# computeModuleDaughterV2.net
KiCad netlist of a schematic drawn in EAGLE
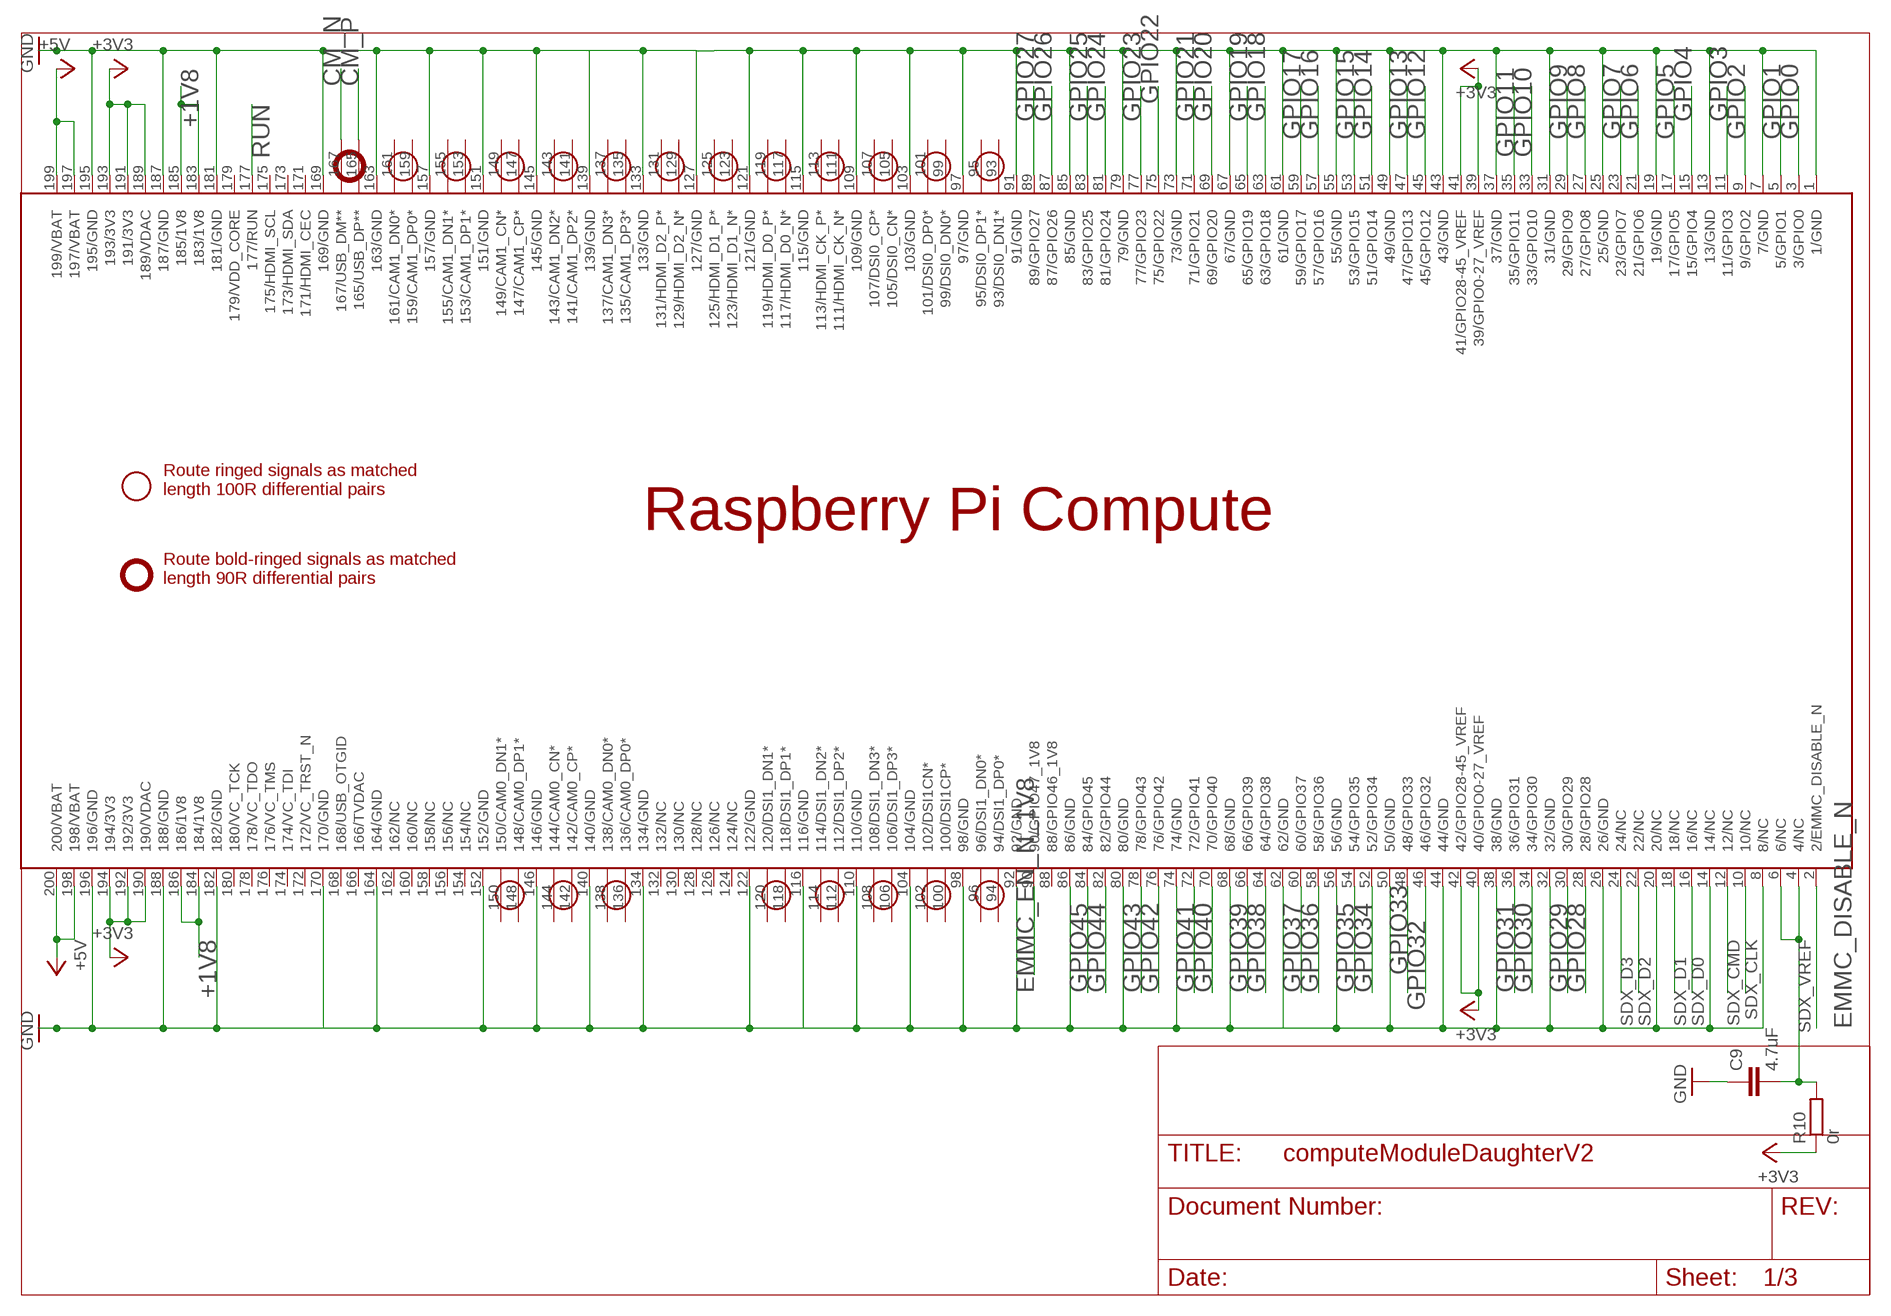
[diagram p0: schematic, sheet 1]
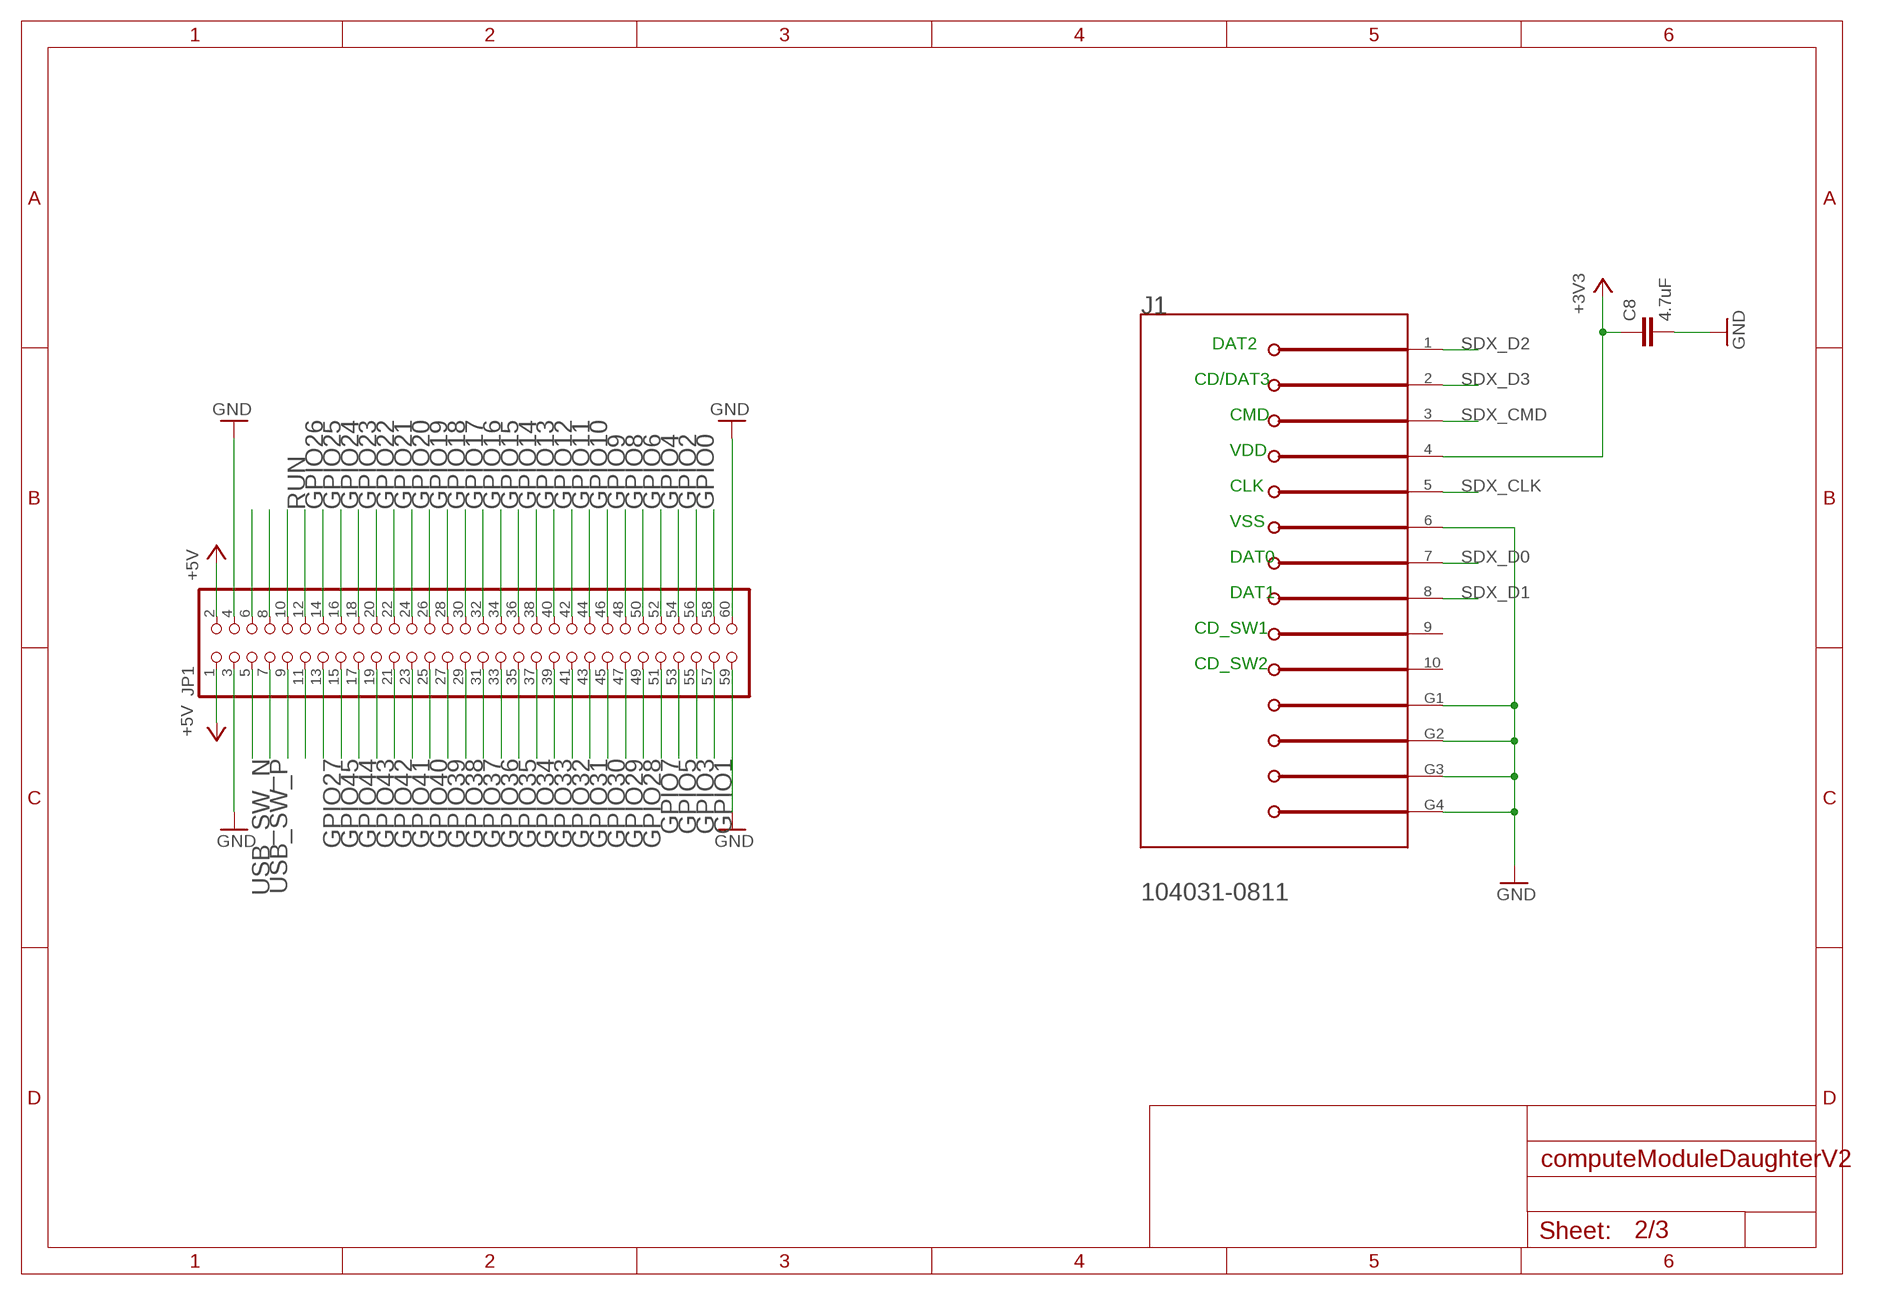
[diagram p1: schematic, sheet 2]
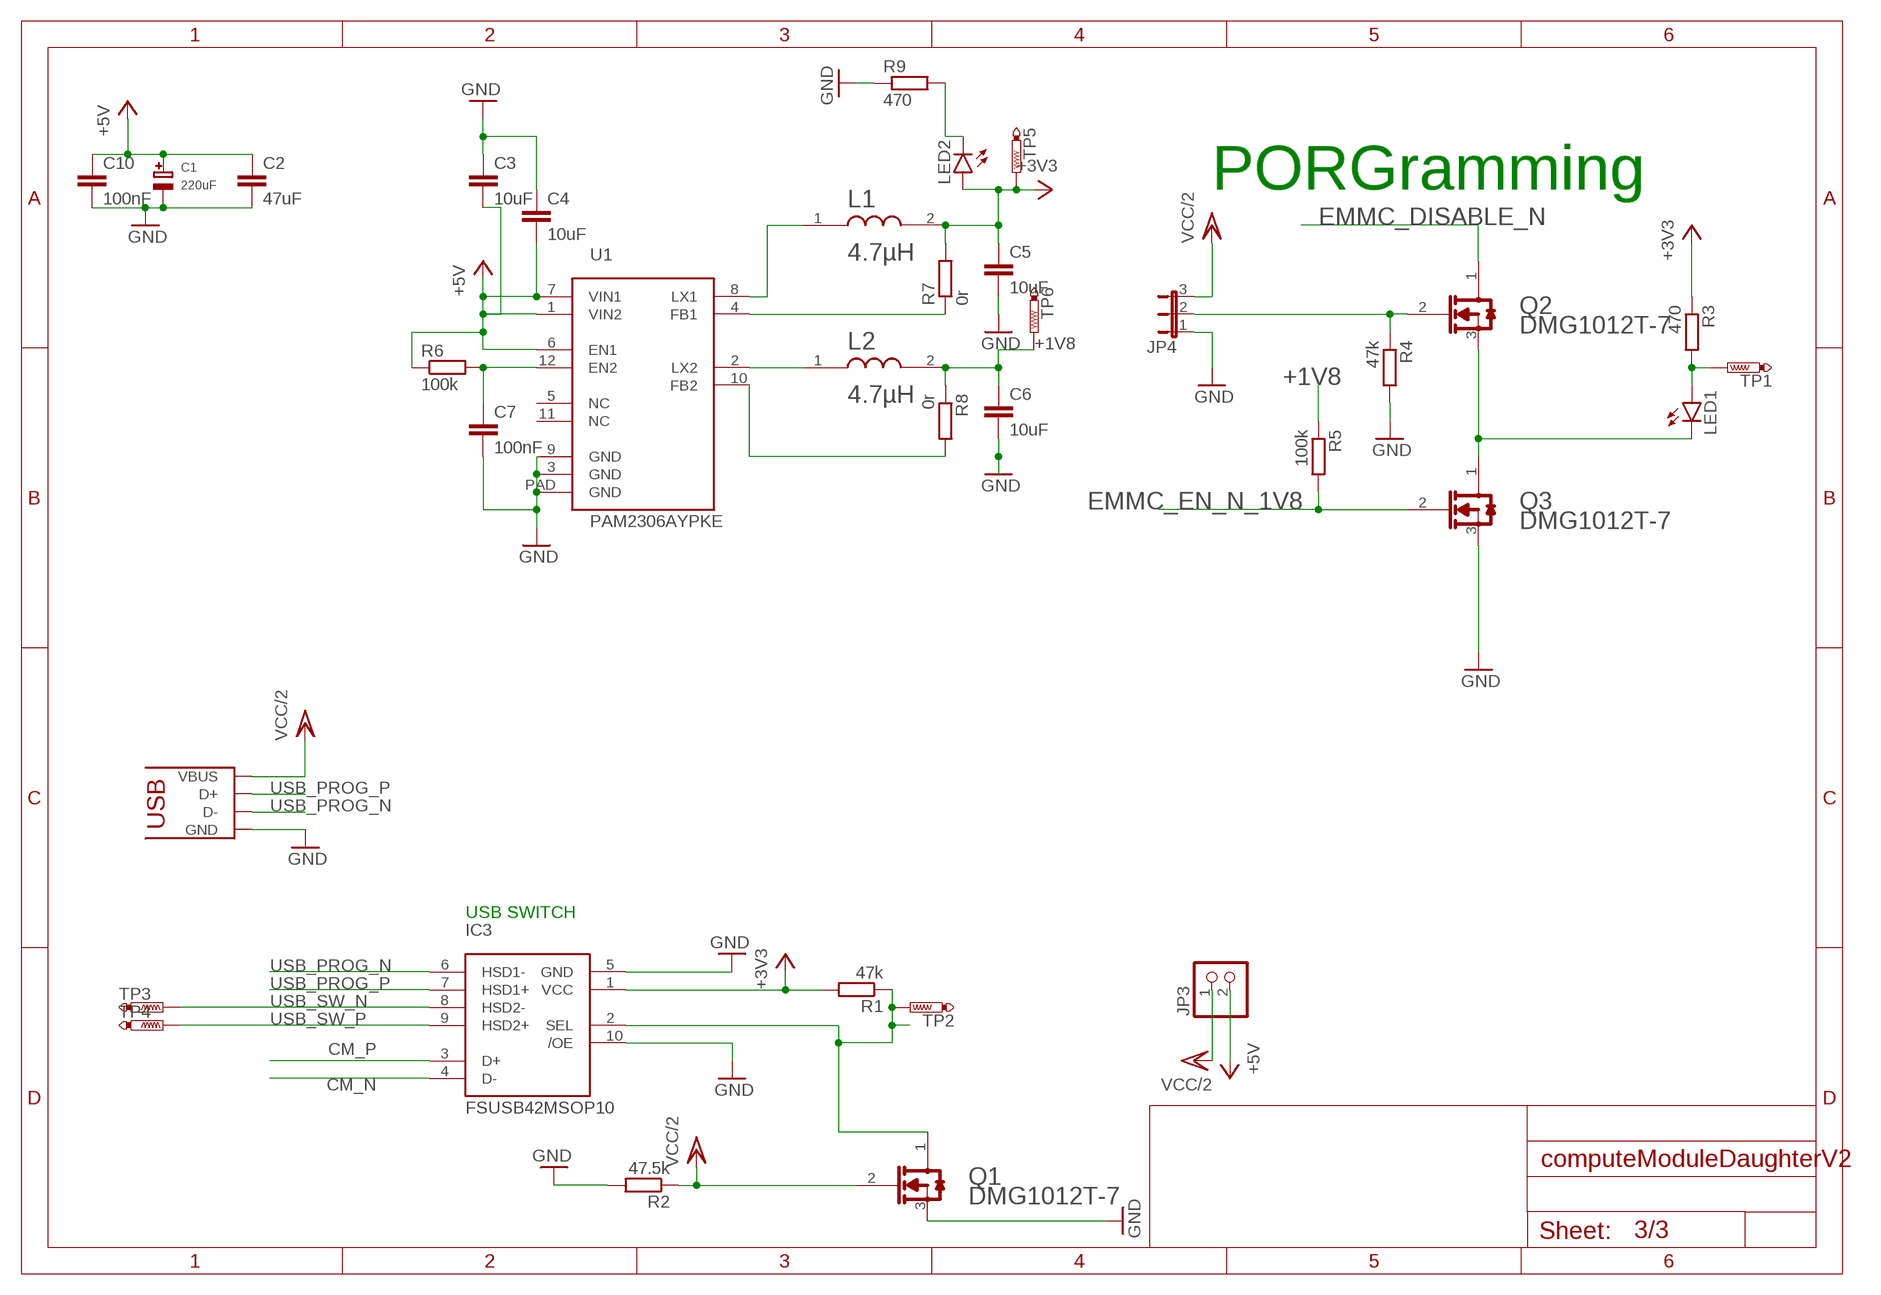
[diagram p2: schematic, sheet 3]

(export (version "E")
  (design (tool "Eeschema 10.0.6"))
  (components
    (comp (ref "C9")
      (value "4.7uF")
      (footprint "eagle-import:C0603")
      (libsource (lib "eagle-import") (part "C-EUC0603"))
    )
    (comp (ref "PCB1")
      (value "RPI_COMPUTE")
      (footprint "eagle-import:RPI_COMPUTE")
      (libsource (lib "eagle-import") (part "RPI_COMPUTE"))
    )
    (comp (ref "R10")
      (value "0r")
      (footprint "eagle-import:R0603")
      (libsource (lib "eagle-import") (part "R-EU_R0603"))
    )
    (comp (ref "C1")
      (value "220uF")
      (footprint "eagle-import:PANASONIC_D")
      (libsource (lib "eagle-import") (part "CAP_ELECTROLYTICPANASONIC_D"))
    )
    (comp (ref "C2")
      (value "47uF")
      (footprint "eagle-import:C1206")
      (libsource (lib "eagle-import") (part "resistor_348_C-EUC1206"))
    )
    (comp (ref "C3")
      (value "10uF")
      (footprint "eagle-import:C0805")
      (libsource (lib "eagle-import") (part "resistor_348_C-EUC0805"))
    )
    (comp (ref "C4")
      (value "10uF")
      (footprint "eagle-import:C0805")
      (libsource (lib "eagle-import") (part "resistor_348_C-EUC0805"))
    )
    (comp (ref "C5")
      (value "10uF")
      (footprint "eagle-import:C0805")
      (libsource (lib "eagle-import") (part "resistor_348_C-EUC0805"))
    )
    (comp (ref "C6")
      (value "10uF")
      (footprint "eagle-import:C0805")
      (libsource (lib "eagle-import") (part "resistor_348_C-EUC0805"))
    )
    (comp (ref "C7")
      (value "100nF")
      (footprint "eagle-import:C0603")
      (libsource (lib "eagle-import") (part "resistor_348_C-EUC0603"))
    )
    (comp (ref "C10")
      (value "100nF")
      (footprint "eagle-import:C0603")
      (libsource (lib "eagle-import") (part "resistor_348_C-EUC0603"))
    )
    (comp (ref "IC3")
      (value "FSUSB42MSOP10")
      (footprint "eagle-import:MSOP10")
      (libsource (lib "eagle-import") (part "FSUSB42MSOP10"))
    )
    (comp (ref "JP2")
      (value "USB-MICROB")
      (footprint "eagle-import:USB-MICROB")
      (libsource (lib "eagle-import") (part "USB-MICROB"))
    )
    (comp (ref "JP3")
      (value "PINHD-1X2")
      (footprint "eagle-import:1X02")
      (libsource (lib "eagle-import") (part "PINHD-1X2"))
    )
    (comp (ref "JP4")
      (value "JP2E")
      (footprint "eagle-import:JP2")
      (libsource (lib "eagle-import") (part "JP2E"))
    )
    (comp (ref "L1")
      (value "BOURNS_SRN4018-4R7MBOURNS_SRN4018-4R7M_0_0")
      (footprint "eagle-import:BOURNS_SRN4018-4R7M_0")
      (fields
        (field (name "DIGIKEY_PART_NUMBER") "SRN4018-4R7MCT-ND")
        (field (name "MF") "Bourns")
        (field (name "MOUSER_PART_NUMBER") "652-SRN4018-4R7M")
      )
      (libsource (lib "eagle-import") (part "BOURNS_SRN4018-4R7MBOURNS_SRN4018-4R7M_0_0"))
    )
    (comp (ref "L2")
      (value "BOURNS_SRN4018-4R7MBOURNS_SRN4018-4R7M_0_0")
      (footprint "eagle-import:BOURNS_SRN4018-4R7M_0")
      (fields
        (field (name "DIGIKEY_PART_NUMBER") "SRN4018-4R7MCT-ND")
        (field (name "MF") "Bourns")
        (field (name "MOUSER_PART_NUMBER") "652-SRN4018-4R7M")
      )
      (libsource (lib "eagle-import") (part "BOURNS_SRN4018-4R7MBOURNS_SRN4018-4R7M_0_0"))
    )
    (comp (ref "LED1")
      (value "LEDCHIP-LED0603")
      (footprint "eagle-import:CHIP-LED0603")
      (libsource (lib "eagle-import") (part "LEDCHIP-LED0603"))
    )
    (comp (ref "LED2")
      (value "LEDCHIP-LED0603")
      (footprint "eagle-import:CHIP-LED0603")
      (libsource (lib "eagle-import") (part "LEDCHIP-LED0603"))
    )
    (comp (ref "Q1")
      (value "DIODES_DMG1012T-7DIODES_DMG1012T-7_0_0")
      (footprint "eagle-import:DIODES_DMG1012T-7_0")
      (fields
        (field (name "DIGIKEY_PART_NUMBER") "DMG1012T-7DICT-ND")
        (field (name "MF") "Diodes")
        (field (name "MOUSER_PART_NUMBER") "621-DMG1012T-7")
      )
      (libsource (lib "eagle-import") (part "DIODES_DMG1012T-7DIODES_DMG1012T-7_0_0"))
    )
    (comp (ref "Q2")
      (value "DIODES_DMG1012T-7DIODES_DMG1012T-7_0_0")
      (footprint "eagle-import:DIODES_DMG1012T-7_0")
      (fields
        (field (name "DIGIKEY_PART_NUMBER") "DMG1012T-7DICT-ND")
        (field (name "MF") "Diodes")
        (field (name "MOUSER_PART_NUMBER") "621-DMG1012T-7")
      )
      (libsource (lib "eagle-import") (part "DIODES_DMG1012T-7DIODES_DMG1012T-7_0_0"))
    )
    (comp (ref "Q3")
      (value "DIODES_DMG1012T-7DIODES_DMG1012T-7_0_0")
      (footprint "eagle-import:DIODES_DMG1012T-7_0")
      (fields
        (field (name "DIGIKEY_PART_NUMBER") "DMG1012T-7DICT-ND")
        (field (name "MF") "Diodes")
        (field (name "MOUSER_PART_NUMBER") "621-DMG1012T-7")
      )
      (libsource (lib "eagle-import") (part "DIODES_DMG1012T-7DIODES_DMG1012T-7_0_0"))
    )
    (comp (ref "R1")
      (value "47k")
      (footprint "eagle-import:R0603")
      (libsource (lib "eagle-import") (part "resistor_348_R-EU_R0603"))
    )
    (comp (ref "R2")
      (value "47.5k")
      (footprint "eagle-import:R0603")
      (libsource (lib "eagle-import") (part "resistor_348_R-EU_R0603"))
    )
    (comp (ref "R3")
      (value "470")
      (footprint "eagle-import:R0603")
      (libsource (lib "eagle-import") (part "resistor_348_R-EU_R0603"))
    )
    (comp (ref "R4")
      (value "47k")
      (footprint "eagle-import:R0603")
      (libsource (lib "eagle-import") (part "resistor_348_R-EU_R0603"))
    )
    (comp (ref "R5")
      (value "100k")
      (footprint "eagle-import:R0603")
      (libsource (lib "eagle-import") (part "resistor_348_R-EU_R0603"))
    )
    (comp (ref "R6")
      (value "100k")
      (footprint "eagle-import:R0603")
      (libsource (lib "eagle-import") (part "resistor_348_R-EU_R0603"))
    )
    (comp (ref "R7")
      (value "0r")
      (footprint "eagle-import:R0603")
      (libsource (lib "eagle-import") (part "resistor_348_R-EU_R0603"))
    )
    (comp (ref "R8")
      (value "0r")
      (footprint "eagle-import:R0603")
      (libsource (lib "eagle-import") (part "resistor_348_R-EU_R0603"))
    )
    (comp (ref "R9")
      (value "470")
      (footprint "eagle-import:R0603")
      (libsource (lib "eagle-import") (part "resistor_348_R-EU_R0603"))
    )
    (comp (ref "TP1")
      (value "PTR1B1,27")
      (footprint "eagle-import:B1,27")
      (libsource (lib "eagle-import") (part "PTR1B1,27"))
    )
    (comp (ref "TP2")
      (value "PTR1B1,27")
      (footprint "eagle-import:B1,27")
      (libsource (lib "eagle-import") (part "PTR1B1,27"))
    )
    (comp (ref "TP3")
      (value "PTR1B1,27")
      (footprint "eagle-import:B1,27")
      (libsource (lib "eagle-import") (part "PTR1B1,27"))
    )
    (comp (ref "TP4")
      (value "PTR1B1,27")
      (footprint "eagle-import:B1,27")
      (libsource (lib "eagle-import") (part "PTR1B1,27"))
    )
    (comp (ref "TP5")
      (value "PTR1B1,27")
      (footprint "eagle-import:B1,27")
      (libsource (lib "eagle-import") (part "PTR1B1,27"))
    )
    (comp (ref "TP6")
      (value "PTR1B1,27")
      (footprint "eagle-import:B1,27")
      (libsource (lib "eagle-import") (part "PTR1B1,27"))
    )
    (comp (ref "U1")
      (value "PAM2306AYPKE")
      (footprint "eagle-import:WDFN-12L")
      (libsource (lib "eagle-import") (part "PAM2306AYPKE"))
    )
    (comp (ref "C8")
      (value "4.7uF")
      (footprint "eagle-import:C0603")
      (libsource (lib "eagle-import") (part "C-EUC0603"))
    )
    (comp (ref "J1")
      (value "MOLEX_104031-0811MOLEX_104031-0811_0_0")
      (footprint "eagle-import:MOLEX_104031-0811_0")
      (fields
        (field (name "DIGIKEY_PART_NUMBER") "WM6357CT-ND")
        (field (name "MF") "Molex")
        (field (name "MPN") "104031-0811")
      )
      (libsource (lib "eagle-import") (part "MOLEX_104031-0811MOLEX_104031-0811_0_0"))
    )
    (comp (ref "JP1")
      (value "PINHD-2X30")
      (footprint "eagle-import:2X30")
      (libsource (lib "eagle-import") (part "PINHD-2X30"))
    )
  )
  (nets
    (net (code "1") (name "+1V8") (class "Default")
      (node (ref "C6") (pin "1") (pinfunction "1_1") (pintype "passive"))
      (node (ref "L2") (pin "2") (pinfunction "2_2") (pintype "bidirectional"))
      (node (ref "PCB1") (pin "183") (pinfunction "183/1V8_183") (pintype "bidirectional"))
      (node (ref "PCB1") (pin "184") (pinfunction "184/1V8_184") (pintype "bidirectional"))
      (node (ref "PCB1") (pin "185") (pinfunction "185/1V8_185") (pintype "bidirectional"))
      (node (ref "PCB1") (pin "186") (pinfunction "186/1V8_186") (pintype "bidirectional"))
      (node (ref "R5") (pin "1") (pinfunction "1_1") (pintype "passive"))
      (node (ref "R8") (pin "1") (pinfunction "1_1") (pintype "passive"))
      (node (ref "TP6") (pin "TP") (pinfunction "TP_TP") (pintype "input"))
    )
    (net (code "2") (name "+3V3") (class "Default")
      (node (ref "C5") (pin "1") (pinfunction "1_1") (pintype "passive"))
      (node (ref "C8") (pin "1") (pinfunction "1_1") (pintype "passive"))
      (node (ref "IC3") (pin "1") (pinfunction "VCC_1") (pintype "bidirectional"))
      (node (ref "J1") (pin "4") (pinfunction "VDD_4") (pintype "power_in"))
      (node (ref "L1") (pin "2") (pinfunction "2_2") (pintype "bidirectional"))
      (node (ref "LED2") (pin "A") (pinfunction "A_A") (pintype "passive"))
      (node (ref "PCB1") (pin "189") (pinfunction "189/VDAC_189") (pintype "bidirectional"))
      (node (ref "PCB1") (pin "190") (pinfunction "190/VDAC_190") (pintype "bidirectional"))
      (node (ref "PCB1") (pin "191") (pinfunction "191/3V3_191") (pintype "bidirectional"))
      (node (ref "PCB1") (pin "192") (pinfunction "192/3V3_192") (pintype "bidirectional"))
      (node (ref "PCB1") (pin "193") (pinfunction "193/3V3_193") (pintype "bidirectional"))
      (node (ref "PCB1") (pin "194") (pinfunction "194/3V3_194") (pintype "bidirectional"))
      (node (ref "PCB1") (pin "39") (pinfunction "39/GPIO0-27_VREF_39") (pintype "bidirectional"))
      (node (ref "PCB1") (pin "40") (pinfunction "40/GPIO0-27_VREF_40") (pintype "bidirectional"))
      (node (ref "PCB1") (pin "41") (pinfunction "41/GPIO28-45_VREF_41") (pintype "bidirectional"))
      (node (ref "PCB1") (pin "42") (pinfunction "42/GPIO28-45_VREF_42") (pintype "bidirectional"))
      (node (ref "R1") (pin "2") (pinfunction "2_2") (pintype "passive"))
      (node (ref "R10") (pin "1") (pinfunction "1_1") (pintype "passive"))
      (node (ref "R3") (pin "1") (pinfunction "1_1") (pintype "passive"))
      (node (ref "R7") (pin "2") (pinfunction "2_2") (pintype "passive"))
      (node (ref "TP5") (pin "TP") (pinfunction "TP_TP") (pintype "input"))
    )
    (net (code "3") (name "+5V") (class "Default")
      (node (ref "C1") (pin "+") (pinfunction "+_+") (pintype "passive"))
      (node (ref "C10") (pin "1") (pinfunction "1_1") (pintype "passive"))
      (node (ref "C2") (pin "1") (pinfunction "1_1") (pintype "passive"))
      (node (ref "C3") (pin "2") (pinfunction "2_2") (pintype "passive"))
      (node (ref "C4") (pin "2") (pinfunction "2_2") (pintype "passive"))
      (node (ref "JP1") (pin "1") (pinfunction "1_1") (pintype "passive"))
      (node (ref "JP1") (pin "2") (pinfunction "2_2") (pintype "passive"))
      (node (ref "JP3") (pin "2") (pinfunction "2_2") (pintype "passive"))
      (node (ref "PCB1") (pin "197") (pinfunction "197/VBAT_197") (pintype "bidirectional"))
      (node (ref "PCB1") (pin "198") (pinfunction "198/VBAT_198") (pintype "bidirectional"))
      (node (ref "PCB1") (pin "199") (pinfunction "199/VBAT_199") (pintype "bidirectional"))
      (node (ref "PCB1") (pin "200") (pinfunction "200/VBAT_200") (pintype "bidirectional"))
      (node (ref "R6") (pin "1") (pinfunction "1_1") (pintype "passive"))
      (node (ref "U1") (pin "1") (pinfunction "VIN2_1") (pintype "power_in"))
      (node (ref "U1") (pin "6") (pinfunction "EN1_6") (pintype "input"))
      (node (ref "U1") (pin "7") (pinfunction "VIN1_7") (pintype "power_in"))
    )
    (net (code "4") (name "CM_N") (class "Default")
      (node (ref "IC3") (pin "4") (pinfunction "D-_4") (pintype "bidirectional"))
      (node (ref "PCB1") (pin "167") (pinfunction "167/USB_DM**_167") (pintype "bidirectional"))
    )
    (net (code "5") (name "CM_P") (class "Default")
      (node (ref "IC3") (pin "3") (pinfunction "D+_3") (pintype "bidirectional"))
      (node (ref "PCB1") (pin "165") (pinfunction "165/USB_DP**_165") (pintype "bidirectional"))
    )
    (net (code "6") (name "EMMC_DISABLE_N") (class "Default")
      (node (ref "PCB1") (pin "2") (pinfunction "2/EMMC_DISABLE_N_2") (pintype "bidirectional"))
      (node (ref "Q2") (pin "1") (pinfunction "DRAIN_1") (pintype "bidirectional"))
    )
    (net (code "7") (name "EMMC_EN_N_1V8") (class "Default")
      (node (ref "PCB1") (pin "90") (pinfunction "90/GPIO47_1V8_90") (pintype "bidirectional"))
      (node (ref "Q3") (pin "2") (pinfunction "GATE_2") (pintype "bidirectional"))
      (node (ref "R5") (pin "2") (pinfunction "2_2") (pintype "passive"))
    )
    (net (code "8") (name "GND") (class "Default")
      (node (ref "C1") (pin "-") (pinfunction "-_-") (pintype "passive"))
      (node (ref "C10") (pin "2") (pinfunction "2_2") (pintype "passive"))
      (node (ref "C2") (pin "2") (pinfunction "2_2") (pintype "passive"))
      (node (ref "C3") (pin "1") (pinfunction "1_1") (pintype "passive"))
      (node (ref "C4") (pin "1") (pinfunction "1_1") (pintype "passive"))
      (node (ref "C5") (pin "2") (pinfunction "2_2") (pintype "passive"))
      (node (ref "C6") (pin "2") (pinfunction "2_2") (pintype "passive"))
      (node (ref "C7") (pin "2") (pinfunction "2_2") (pintype "passive"))
      (node (ref "C8") (pin "2") (pinfunction "2_2") (pintype "passive"))
      (node (ref "C9") (pin "1") (pinfunction "1_1") (pintype "passive"))
      (node (ref "IC3") (pin "10") (pinfunction "/OE_10") (pintype "bidirectional"))
      (node (ref "IC3") (pin "5") (pinfunction "GND_5") (pintype "bidirectional"))
      (node (ref "J1") (pin "6") (pinfunction "VSS_6") (pintype "power_in"))
      (node (ref "J1") (pin "G1") (pinfunction "G1_G1") (pintype "passive"))
      (node (ref "J1") (pin "G2") (pinfunction "G2_G2") (pintype "passive"))
      (node (ref "J1") (pin "G3") (pinfunction "G3_G3") (pintype "passive"))
      (node (ref "J1") (pin "G4") (pinfunction "G4_G4") (pintype "passive"))
      (node (ref "JP1") (pin "3") (pinfunction "3_3") (pintype "passive"))
      (node (ref "JP1") (pin "4") (pinfunction "4_4") (pintype "passive"))
      (node (ref "JP1") (pin "59") (pinfunction "59_59") (pintype "passive"))
      (node (ref "JP1") (pin "60") (pinfunction "60_60") (pintype "passive"))
      (node (ref "JP2") (pin "GND") (pinfunction "GND_GND") (pintype "bidirectional"))
      (node (ref "JP2") (pin "MT1") (pinfunction "GND_MT1") (pintype "bidirectional"))
      (node (ref "JP2") (pin "MT2") (pinfunction "GND_MT2") (pintype "bidirectional"))
      (node (ref "JP2") (pin "P$1") (pinfunction "GND_P$1") (pintype "bidirectional"))
      (node (ref "JP2") (pin "P$2") (pinfunction "GND_P$2") (pintype "bidirectional"))
      (node (ref "JP2") (pin "P$3") (pinfunction "GND_P$3") (pintype "bidirectional"))
      (node (ref "JP2") (pin "P$4") (pinfunction "GND_P$4") (pintype "bidirectional"))
      (node (ref "JP4") (pin "1") (pinfunction "1_1") (pintype "passive"))
      (node (ref "PCB1") (pin "1") (pinfunction "1/GND_1") (pintype "bidirectional"))
      (node (ref "PCB1") (pin "103") (pinfunction "103/GND_103") (pintype "bidirectional"))
      (node (ref "PCB1") (pin "104") (pinfunction "104/GND_104") (pintype "bidirectional"))
      (node (ref "PCB1") (pin "109") (pinfunction "109/GND_109") (pintype "bidirectional"))
      (node (ref "PCB1") (pin "110") (pinfunction "110/GND_110") (pintype "bidirectional"))
      (node (ref "PCB1") (pin "115") (pinfunction "115/GND_115") (pintype "bidirectional"))
      (node (ref "PCB1") (pin "116") (pinfunction "116/GND_116") (pintype "bidirectional"))
      (node (ref "PCB1") (pin "121") (pinfunction "121/GND_121") (pintype "bidirectional"))
      (node (ref "PCB1") (pin "122") (pinfunction "122/GND_122") (pintype "bidirectional"))
      (node (ref "PCB1") (pin "127") (pinfunction "127/GND_127") (pintype "bidirectional"))
      (node (ref "PCB1") (pin "13") (pinfunction "13/GND_13") (pintype "bidirectional"))
      (node (ref "PCB1") (pin "133") (pinfunction "133/GND_133") (pintype "bidirectional"))
      (node (ref "PCB1") (pin "134") (pinfunction "134/GND_134") (pintype "bidirectional"))
      (node (ref "PCB1") (pin "139") (pinfunction "139/GND_139") (pintype "bidirectional"))
      (node (ref "PCB1") (pin "14") (pinfunction "14/NC_14") (pintype "bidirectional"))
      (node (ref "PCB1") (pin "140") (pinfunction "140/GND_140") (pintype "bidirectional"))
      (node (ref "PCB1") (pin "145") (pinfunction "145/GND_145") (pintype "bidirectional"))
      (node (ref "PCB1") (pin "146") (pinfunction "146/GND_146") (pintype "bidirectional"))
      (node (ref "PCB1") (pin "151") (pinfunction "151/GND_151") (pintype "bidirectional"))
      (node (ref "PCB1") (pin "152") (pinfunction "152/GND_152") (pintype "bidirectional"))
      (node (ref "PCB1") (pin "157") (pinfunction "157/GND_157") (pintype "bidirectional"))
      (node (ref "PCB1") (pin "163") (pinfunction "163/GND_163") (pintype "bidirectional"))
      (node (ref "PCB1") (pin "164") (pinfunction "164/GND_164") (pintype "bidirectional"))
      (node (ref "PCB1") (pin "169") (pinfunction "169/GND_169") (pintype "bidirectional"))
      (node (ref "PCB1") (pin "170") (pinfunction "170/GND_170") (pintype "bidirectional"))
      (node (ref "PCB1") (pin "181") (pinfunction "181/GND_181") (pintype "bidirectional"))
      (node (ref "PCB1") (pin "182") (pinfunction "182/GND_182") (pintype "bidirectional"))
      (node (ref "PCB1") (pin "187") (pinfunction "187/GND_187") (pintype "bidirectional"))
      (node (ref "PCB1") (pin "188") (pinfunction "188/GND_188") (pintype "bidirectional"))
      (node (ref "PCB1") (pin "19") (pinfunction "19/GND_19") (pintype "bidirectional"))
      (node (ref "PCB1") (pin "195") (pinfunction "195/GND_195") (pintype "bidirectional"))
      (node (ref "PCB1") (pin "196") (pinfunction "196/GND_196") (pintype "bidirectional"))
      (node (ref "PCB1") (pin "20") (pinfunction "20/NC_20") (pintype "bidirectional"))
      (node (ref "PCB1") (pin "25") (pinfunction "25/GND_25") (pintype "bidirectional"))
      (node (ref "PCB1") (pin "26") (pinfunction "26/GND_26") (pintype "bidirectional"))
      (node (ref "PCB1") (pin "31") (pinfunction "31/GND_31") (pintype "bidirectional"))
      (node (ref "PCB1") (pin "32") (pinfunction "32/GND_32") (pintype "bidirectional"))
      (node (ref "PCB1") (pin "37") (pinfunction "37/GND_37") (pintype "bidirectional"))
      (node (ref "PCB1") (pin "38") (pinfunction "38/GND_38") (pintype "bidirectional"))
      (node (ref "PCB1") (pin "43") (pinfunction "43/GND_43") (pintype "bidirectional"))
      (node (ref "PCB1") (pin "44") (pinfunction "44/GND_44") (pintype "bidirectional"))
      (node (ref "PCB1") (pin "49") (pinfunction "49/GND_49") (pintype "bidirectional"))
      (node (ref "PCB1") (pin "50") (pinfunction "50/GND_50") (pintype "bidirectional"))
      (node (ref "PCB1") (pin "55") (pinfunction "55/GND_55") (pintype "bidirectional"))
      (node (ref "PCB1") (pin "56") (pinfunction "56/GND_56") (pintype "bidirectional"))
      (node (ref "PCB1") (pin "61") (pinfunction "61/GND_61") (pintype "bidirectional"))
      (node (ref "PCB1") (pin "62") (pinfunction "62/GND_62") (pintype "bidirectional"))
      (node (ref "PCB1") (pin "67") (pinfunction "67/GND_67") (pintype "bidirectional"))
      (node (ref "PCB1") (pin "68") (pinfunction "68/GND_68") (pintype "bidirectional"))
      (node (ref "PCB1") (pin "7") (pinfunction "7/GND_7") (pintype "bidirectional"))
      (node (ref "PCB1") (pin "73") (pinfunction "73/GND_73") (pintype "bidirectional"))
      (node (ref "PCB1") (pin "74") (pinfunction "74/GND_74") (pintype "bidirectional"))
      (node (ref "PCB1") (pin "79") (pinfunction "79/GND_79") (pintype "bidirectional"))
      (node (ref "PCB1") (pin "8") (pinfunction "8/NC_8") (pintype "bidirectional"))
      (node (ref "PCB1") (pin "80") (pinfunction "80/GND_80") (pintype "bidirectional"))
      (node (ref "PCB1") (pin "85") (pinfunction "85/GND_85") (pintype "bidirectional"))
      (node (ref "PCB1") (pin "86") (pinfunction "86/GND_86") (pintype "bidirectional"))
      (node (ref "PCB1") (pin "91") (pinfunction "91/GND_91") (pintype "bidirectional"))
      (node (ref "PCB1") (pin "92") (pinfunction "92/GND_92") (pintype "bidirectional"))
      (node (ref "PCB1") (pin "97") (pinfunction "97/GND_97") (pintype "bidirectional"))
      (node (ref "PCB1") (pin "98") (pinfunction "98/GND_98") (pintype "bidirectional"))
      (node (ref "Q1") (pin "3") (pinfunction "SOURCE_3") (pintype "bidirectional"))
      (node (ref "Q3") (pin "3") (pinfunction "SOURCE_3") (pintype "bidirectional"))
      (node (ref "R2") (pin "2") (pinfunction "2_2") (pintype "passive"))
      (node (ref "R4") (pin "2") (pinfunction "2_2") (pintype "passive"))
      (node (ref "R9") (pin "1") (pinfunction "1_1") (pintype "passive"))
      (node (ref "U1") (pin "3") (pinfunction "GND_3") (pintype "power_in"))
      (node (ref "U1") (pin "9") (pinfunction "GND_9") (pintype "power_in"))
      (node (ref "U1") (pin "PAD") (pinfunction "GND_PAD") (pintype "power_in"))
    )
    (net (code "9") (name "GPIO0") (class "Default")
      (node (ref "JP1") (pin "58") (pinfunction "58_58") (pintype "passive"))
      (node (ref "PCB1") (pin "3") (pinfunction "3/GPIO0_3") (pintype "bidirectional"))
    )
    (net (code "10") (name "GPIO1") (class "Default")
      (node (ref "JP1") (pin "57") (pinfunction "57_57") (pintype "passive"))
      (node (ref "PCB1") (pin "5") (pinfunction "5/GPIO1_5") (pintype "bidirectional"))
    )
    (net (code "11") (name "GPIO2") (class "Default")
      (node (ref "JP1") (pin "56") (pinfunction "56_56") (pintype "passive"))
      (node (ref "PCB1") (pin "9") (pinfunction "9/GPIO2_9") (pintype "bidirectional"))
    )
    (net (code "12") (name "GPIO3") (class "Default")
      (node (ref "JP1") (pin "55") (pinfunction "55_55") (pintype "passive"))
      (node (ref "PCB1") (pin "11") (pinfunction "11/GPIO3_11") (pintype "bidirectional"))
    )
    (net (code "13") (name "GPIO4") (class "Default")
      (node (ref "JP1") (pin "54") (pinfunction "54_54") (pintype "passive"))
      (node (ref "PCB1") (pin "15") (pinfunction "15/GPIO4_15") (pintype "bidirectional"))
    )
    (net (code "14") (name "GPIO5") (class "Default")
      (node (ref "JP1") (pin "53") (pinfunction "53_53") (pintype "passive"))
      (node (ref "PCB1") (pin "17") (pinfunction "17/GPIO5_17") (pintype "bidirectional"))
    )
    (net (code "15") (name "GPIO6") (class "Default")
      (node (ref "JP1") (pin "52") (pinfunction "52_52") (pintype "passive"))
      (node (ref "PCB1") (pin "21") (pinfunction "21/GPIO6_21") (pintype "bidirectional"))
    )
    (net (code "16") (name "GPIO7") (class "Default")
      (node (ref "JP1") (pin "51") (pinfunction "51_51") (pintype "passive"))
      (node (ref "PCB1") (pin "23") (pinfunction "23/GPIO7_23") (pintype "bidirectional"))
    )
    (net (code "17") (name "GPIO8") (class "Default")
      (node (ref "JP1") (pin "50") (pinfunction "50_50") (pintype "passive"))
      (node (ref "PCB1") (pin "27") (pinfunction "27/GPIO8_27") (pintype "bidirectional"))
    )
    (net (code "18") (name "GPIO9") (class "Default")
      (node (ref "JP1") (pin "48") (pinfunction "48_48") (pintype "passive"))
      (node (ref "PCB1") (pin "29") (pinfunction "29/GPIO9_29") (pintype "bidirectional"))
    )
    (net (code "19") (name "GPIO10") (class "Default")
      (node (ref "JP1") (pin "46") (pinfunction "46_46") (pintype "passive"))
      (node (ref "PCB1") (pin "33") (pinfunction "33/GPIO10_33") (pintype "bidirectional"))
    )
    (net (code "20") (name "GPIO11") (class "Default")
      (node (ref "JP1") (pin "44") (pinfunction "44_44") (pintype "passive"))
      (node (ref "PCB1") (pin "35") (pinfunction "35/GPIO11_35") (pintype "bidirectional"))
    )
    (net (code "21") (name "GPIO12") (class "Default")
      (node (ref "JP1") (pin "42") (pinfunction "42_42") (pintype "passive"))
      (node (ref "PCB1") (pin "45") (pinfunction "45/GPIO12_45") (pintype "bidirectional"))
    )
    (net (code "22") (name "GPIO13") (class "Default")
      (node (ref "JP1") (pin "40") (pinfunction "40_40") (pintype "passive"))
      (node (ref "PCB1") (pin "47") (pinfunction "47/GPIO13_47") (pintype "bidirectional"))
    )
    (net (code "23") (name "GPIO14") (class "Default")
      (node (ref "JP1") (pin "38") (pinfunction "38_38") (pintype "passive"))
      (node (ref "PCB1") (pin "51") (pinfunction "51/GPIO14_51") (pintype "bidirectional"))
    )
    (net (code "24") (name "GPIO15") (class "Default")
      (node (ref "JP1") (pin "36") (pinfunction "36_36") (pintype "passive"))
      (node (ref "PCB1") (pin "53") (pinfunction "53/GPIO15_53") (pintype "bidirectional"))
    )
    (net (code "25") (name "GPIO16") (class "Default")
      (node (ref "JP1") (pin "34") (pinfunction "34_34") (pintype "passive"))
      (node (ref "PCB1") (pin "57") (pinfunction "57/GPIO16_57") (pintype "bidirectional"))
    )
    (net (code "26") (name "GPIO17") (class "Default")
      (node (ref "JP1") (pin "32") (pinfunction "32_32") (pintype "passive"))
      (node (ref "PCB1") (pin "59") (pinfunction "59/GPIO17_59") (pintype "bidirectional"))
    )
    (net (code "27") (name "GPIO18") (class "Default")
      (node (ref "JP1") (pin "30") (pinfunction "30_30") (pintype "passive"))
      (node (ref "PCB1") (pin "63") (pinfunction "63/GPIO18_63") (pintype "bidirectional"))
    )
    (net (code "28") (name "GPIO19") (class "Default")
      (node (ref "JP1") (pin "28") (pinfunction "28_28") (pintype "passive"))
      (node (ref "PCB1") (pin "65") (pinfunction "65/GPIO19_65") (pintype "bidirectional"))
    )
    (net (code "29") (name "GPIO20") (class "Default")
      (node (ref "JP1") (pin "26") (pinfunction "26_26") (pintype "passive"))
      (node (ref "PCB1") (pin "69") (pinfunction "69/GPIO20_69") (pintype "bidirectional"))
    )
    (net (code "30") (name "GPIO21") (class "Default")
      (node (ref "JP1") (pin "24") (pinfunction "24_24") (pintype "passive"))
      (node (ref "PCB1") (pin "71") (pinfunction "71/GPIO21_71") (pintype "bidirectional"))
    )
    (net (code "31") (name "GPIO22") (class "Default")
      (node (ref "JP1") (pin "22") (pinfunction "22_22") (pintype "passive"))
      (node (ref "PCB1") (pin "75") (pinfunction "75/GPIO22_75") (pintype "bidirectional"))
    )
    (net (code "32") (name "GPIO23") (class "Default")
      (node (ref "JP1") (pin "20") (pinfunction "20_20") (pintype "passive"))
      (node (ref "PCB1") (pin "77") (pinfunction "77/GPIO23_77") (pintype "bidirectional"))
    )
    (net (code "33") (name "GPIO24") (class "Default")
      (node (ref "JP1") (pin "18") (pinfunction "18_18") (pintype "passive"))
      (node (ref "PCB1") (pin "81") (pinfunction "81/GPIO24_81") (pintype "bidirectional"))
    )
    (net (code "34") (name "GPIO25") (class "Default")
      (node (ref "JP1") (pin "16") (pinfunction "16_16") (pintype "passive"))
      (node (ref "PCB1") (pin "83") (pinfunction "83/GPIO25_83") (pintype "bidirectional"))
    )
    (net (code "35") (name "GPIO26") (class "Default")
      (node (ref "JP1") (pin "14") (pinfunction "14_14") (pintype "passive"))
      (node (ref "PCB1") (pin "87") (pinfunction "87/GPIO26_87") (pintype "bidirectional"))
    )
    (net (code "36") (name "GPIO27") (class "Default")
      (node (ref "JP1") (pin "13") (pinfunction "13_13") (pintype "passive"))
      (node (ref "PCB1") (pin "89") (pinfunction "89/GPIO27_89") (pintype "bidirectional"))
    )
    (net (code "37") (name "GPIO28") (class "Default")
      (node (ref "JP1") (pin "49") (pinfunction "49_49") (pintype "passive"))
      (node (ref "PCB1") (pin "28") (pinfunction "28/GPIO28_28") (pintype "bidirectional"))
    )
    (net (code "38") (name "GPIO29") (class "Default")
      (node (ref "JP1") (pin "47") (pinfunction "47_47") (pintype "passive"))
      (node (ref "PCB1") (pin "30") (pinfunction "30/GPIO29_30") (pintype "bidirectional"))
    )
    (net (code "39") (name "GPIO30") (class "Default")
      (node (ref "JP1") (pin "45") (pinfunction "45_45") (pintype "passive"))
      (node (ref "PCB1") (pin "34") (pinfunction "34/GPIO30_34") (pintype "bidirectional"))
    )
    (net (code "40") (name "GPIO31") (class "Default")
      (node (ref "JP1") (pin "43") (pinfunction "43_43") (pintype "passive"))
      (node (ref "PCB1") (pin "36") (pinfunction "36/GPIO31_36") (pintype "bidirectional"))
    )
    (net (code "41") (name "GPIO32") (class "Default")
      (node (ref "JP1") (pin "41") (pinfunction "41_41") (pintype "passive"))
      (node (ref "PCB1") (pin "46") (pinfunction "46/GPIO32_46") (pintype "bidirectional"))
    )
    (net (code "42") (name "GPIO33") (class "Default")
      (node (ref "JP1") (pin "39") (pinfunction "39_39") (pintype "passive"))
      (node (ref "PCB1") (pin "48") (pinfunction "48/GPIO33_48") (pintype "bidirectional"))
    )
    (net (code "43") (name "GPIO34") (class "Default")
      (node (ref "JP1") (pin "37") (pinfunction "37_37") (pintype "passive"))
      (node (ref "PCB1") (pin "52") (pinfunction "52/GPIO34_52") (pintype "bidirectional"))
    )
    (net (code "44") (name "GPIO35") (class "Default")
      (node (ref "JP1") (pin "35") (pinfunction "35_35") (pintype "passive"))
      (node (ref "PCB1") (pin "54") (pinfunction "54/GPIO35_54") (pintype "bidirectional"))
    )
    (net (code "45") (name "GPIO36") (class "Default")
      (node (ref "JP1") (pin "33") (pinfunction "33_33") (pintype "passive"))
      (node (ref "PCB1") (pin "58") (pinfunction "58/GPIO36_58") (pintype "bidirectional"))
    )
    (net (code "46") (name "GPIO37") (class "Default")
      (node (ref "JP1") (pin "31") (pinfunction "31_31") (pintype "passive"))
      (node (ref "PCB1") (pin "60") (pinfunction "60/GPIO37_60") (pintype "bidirectional"))
    )
    (net (code "47") (name "GPIO38") (class "Default")
      (node (ref "JP1") (pin "29") (pinfunction "29_29") (pintype "passive"))
      (node (ref "PCB1") (pin "64") (pinfunction "64/GPIO38_64") (pintype "bidirectional"))
    )
    (net (code "48") (name "GPIO39") (class "Default")
      (node (ref "JP1") (pin "27") (pinfunction "27_27") (pintype "passive"))
      (node (ref "PCB1") (pin "66") (pinfunction "66/GPIO39_66") (pintype "bidirectional"))
    )
    (net (code "49") (name "GPIO40") (class "Default")
      (node (ref "JP1") (pin "25") (pinfunction "25_25") (pintype "passive"))
      (node (ref "PCB1") (pin "70") (pinfunction "70/GPIO40_70") (pintype "bidirectional"))
    )
    (net (code "50") (name "GPIO41") (class "Default")
      (node (ref "JP1") (pin "23") (pinfunction "23_23") (pintype "passive"))
      (node (ref "PCB1") (pin "72") (pinfunction "72/GPIO41_72") (pintype "bidirectional"))
    )
    (net (code "51") (name "GPIO42") (class "Default")
      (node (ref "JP1") (pin "21") (pinfunction "21_21") (pintype "passive"))
      (node (ref "PCB1") (pin "76") (pinfunction "76/GPIO42_76") (pintype "bidirectional"))
    )
    (net (code "52") (name "GPIO43") (class "Default")
      (node (ref "JP1") (pin "19") (pinfunction "19_19") (pintype "passive"))
      (node (ref "PCB1") (pin "78") (pinfunction "78/GPIO43_78") (pintype "bidirectional"))
    )
    (net (code "53") (name "GPIO44") (class "Default")
      (node (ref "JP1") (pin "17") (pinfunction "17_17") (pintype "passive"))
      (node (ref "PCB1") (pin "82") (pinfunction "82/GPIO44_82") (pintype "bidirectional"))
    )
    (net (code "54") (name "GPIO45") (class "Default")
      (node (ref "JP1") (pin "15") (pinfunction "15_15") (pintype "passive"))
      (node (ref "PCB1") (pin "84") (pinfunction "84/GPIO45_84") (pintype "bidirectional"))
    )
    (net (code "55") (name "Net-(IC3-SEL)") (class "Default")
      (node (ref "IC3") (pin "2") (pinfunction "SEL_2") (pintype "bidirectional"))
      (node (ref "Q1") (pin "1") (pinfunction "DRAIN_1") (pintype "bidirectional"))
      (node (ref "R1") (pin "1") (pinfunction "1_1") (pintype "passive"))
      (node (ref "TP2") (pin "TP") (pinfunction "TP_TP") (pintype "input"))
    )
    (net (code "56") (name "Net-(LED1-PadA)") (class "Default")
      (node (ref "LED1") (pin "A") (pinfunction "A_A") (pintype "passive"))
      (node (ref "R3") (pin "2") (pinfunction "2_2") (pintype "passive"))
      (node (ref "TP1") (pin "TP") (pinfunction "TP_TP") (pintype "input"))
    )
    (net (code "57") (name "Net-(LED2-PadC)") (class "Default")
      (node (ref "LED2") (pin "C") (pinfunction "C_C") (pintype "passive"))
      (node (ref "R9") (pin "2") (pinfunction "2_2") (pintype "passive"))
    )
    (net (code "58") (name "Net-(Q2-GATE)") (class "Default")
      (node (ref "JP4") (pin "2") (pinfunction "2_2") (pintype "passive"))
      (node (ref "Q2") (pin "2") (pinfunction "GATE_2") (pintype "bidirectional"))
      (node (ref "R4") (pin "1") (pinfunction "1_1") (pintype "passive"))
    )
    (net (code "59") (name "Net-(Q2-SOURCE)") (class "Default")
      (node (ref "LED1") (pin "C") (pinfunction "C_C") (pintype "passive"))
      (node (ref "Q2") (pin "3") (pinfunction "SOURCE_3") (pintype "bidirectional"))
      (node (ref "Q3") (pin "1") (pinfunction "DRAIN_1") (pintype "bidirectional"))
    )
    (net (code "60") (name "Net-(U1-EN2)") (class "Default")
      (node (ref "C7") (pin "1") (pinfunction "1_1") (pintype "passive"))
      (node (ref "R6") (pin "2") (pinfunction "2_2") (pintype "passive"))
      (node (ref "U1") (pin "12") (pinfunction "EN2_12") (pintype "input"))
    )
    (net (code "61") (name "Net-(U1-FB1)") (class "Default")
      (node (ref "R7") (pin "1") (pinfunction "1_1") (pintype "passive"))
      (node (ref "U1") (pin "4") (pinfunction "FB1_4") (pintype "input"))
    )
    (net (code "62") (name "Net-(U1-FB2)") (class "Default")
      (node (ref "R8") (pin "2") (pinfunction "2_2") (pintype "passive"))
      (node (ref "U1") (pin "10") (pinfunction "FB2_10") (pintype "input"))
    )
    (net (code "63") (name "Net-(U1-LX1)") (class "Default")
      (node (ref "L1") (pin "1") (pinfunction "1_1") (pintype "bidirectional"))
      (node (ref "U1") (pin "8") (pinfunction "LX1_8") (pintype "power_in"))
    )
    (net (code "64") (name "Net-(U1-LX2)") (class "Default")
      (node (ref "L2") (pin "1") (pinfunction "1_1") (pintype "bidirectional"))
      (node (ref "U1") (pin "2") (pinfunction "LX2_2") (pintype "power_in"))
    )
    (net (code "65") (name "RUN") (class "Default")
      (node (ref "JP1") (pin "12") (pinfunction "12_12") (pintype "passive"))
      (node (ref "PCB1") (pin "177") (pinfunction "177/RUN_177") (pintype "bidirectional"))
    )
    (net (code "66") (name "SDX_CLK") (class "Default")
      (node (ref "J1") (pin "5") (pinfunction "CLK_5") (pintype "input"))
      (node (ref "PCB1") (pin "10") (pinfunction "10/NC_10") (pintype "bidirectional"))
    )
    (net (code "67") (name "SDX_CMD") (class "Default")
      (node (ref "J1") (pin "3") (pinfunction "CMD_3") (pintype "bidirectional"))
      (node (ref "PCB1") (pin "12") (pinfunction "12/NC_12") (pintype "bidirectional"))
    )
    (net (code "68") (name "SDX_D0") (class "Default")
      (node (ref "J1") (pin "7") (pinfunction "DAT0_7") (pintype "bidirectional"))
      (node (ref "PCB1") (pin "16") (pinfunction "16/NC_16") (pintype "bidirectional"))
    )
    (net (code "69") (name "SDX_D1") (class "Default")
      (node (ref "J1") (pin "8") (pinfunction "DAT1_8") (pintype "bidirectional"))
      (node (ref "PCB1") (pin "18") (pinfunction "18/NC_18") (pintype "bidirectional"))
    )
    (net (code "70") (name "SDX_D2") (class "Default")
      (node (ref "J1") (pin "1") (pinfunction "DAT2_1") (pintype "bidirectional"))
      (node (ref "PCB1") (pin "22") (pinfunction "22/NC_22") (pintype "bidirectional"))
    )
    (net (code "71") (name "SDX_D3") (class "Default")
      (node (ref "J1") (pin "2") (pinfunction "CD/DAT3_2") (pintype "bidirectional"))
      (node (ref "PCB1") (pin "24") (pinfunction "24/NC_24") (pintype "bidirectional"))
    )
    (net (code "72") (name "SDX_VREF") (class "Default")
      (node (ref "C9") (pin "2") (pinfunction "2_2") (pintype "passive"))
      (node (ref "PCB1") (pin "4") (pinfunction "4/NC_4") (pintype "bidirectional"))
      (node (ref "PCB1") (pin "6") (pinfunction "6/NC_6") (pintype "bidirectional"))
      (node (ref "R10") (pin "2") (pinfunction "2_2") (pintype "passive"))
    )
    (net (code "73") (name "USB_PROG_N") (class "Default")
      (node (ref "IC3") (pin "6") (pinfunction "HSD1-_6") (pintype "bidirectional"))
      (node (ref "JP2") (pin "D-") (pinfunction "D-_D-") (pintype "bidirectional"))
    )
    (net (code "74") (name "USB_PROG_P") (class "Default")
      (node (ref "IC3") (pin "7") (pinfunction "HSD1+_7") (pintype "bidirectional"))
      (node (ref "JP2") (pin "D+") (pinfunction "D+_D+") (pintype "bidirectional"))
    )
    (net (code "75") (name "USB_SW_N") (class "Default")
      (node (ref "IC3") (pin "8") (pinfunction "HSD2-_8") (pintype "bidirectional"))
      (node (ref "JP1") (pin "5") (pinfunction "5_5") (pintype "passive"))
      (node (ref "TP3") (pin "TP") (pinfunction "TP_TP") (pintype "input"))
    )
    (net (code "76") (name "USB_SW_P") (class "Default")
      (node (ref "IC3") (pin "9") (pinfunction "HSD2+_9") (pintype "bidirectional"))
      (node (ref "JP1") (pin "7") (pinfunction "7_7") (pintype "passive"))
      (node (ref "TP4") (pin "TP") (pinfunction "TP_TP") (pintype "input"))
    )
    (net (code "77") (name "VCC{slash}2") (class "Default")
      (node (ref "JP2") (pin "VBUS") (pinfunction "VBUS_VBUS") (pintype "bidirectional"))
      (node (ref "JP3") (pin "1") (pinfunction "1_1") (pintype "passive"))
      (node (ref "JP4") (pin "3") (pinfunction "3_3") (pintype "passive"))
      (node (ref "Q1") (pin "2") (pinfunction "GATE_2") (pintype "bidirectional"))
      (node (ref "R2") (pin "1") (pinfunction "1_1") (pintype "passive"))
    )
    (net (code "78") (name "unconnected-(J1-1_CARD_DETECT_SWITCH-Pad9)") (class "Default")
      (node (ref "J1") (pin "9") (pinfunction "1_CARD_DETECT_SWITCH_9") (pintype "passive"))
    )
    (net (code "79") (name "unconnected-(J1-2_CARD_DETECT_SWITCH-Pad10)") (class "Default")
      (node (ref "J1") (pin "10") (pinfunction "2_CARD_DETECT_SWITCH_10") (pintype "passive"))
    )
    (net (code "80") (name "unconnected-(JP1-Pad6)") (class "Default")
      (node (ref "JP1") (pin "6") (pinfunction "6_6") (pintype "passive"))
    )
    (net (code "81") (name "unconnected-(JP1-Pad8)") (class "Default")
      (node (ref "JP1") (pin "8") (pinfunction "8_8") (pintype "passive"))
    )
    (net (code "82") (name "unconnected-(JP1-Pad9)") (class "Default")
      (node (ref "JP1") (pin "9") (pinfunction "9_9") (pintype "passive"))
    )
    (net (code "83") (name "unconnected-(JP1-Pad10)") (class "Default")
      (node (ref "JP1") (pin "10") (pinfunction "10_10") (pintype "passive"))
    )
    (net (code "84") (name "unconnected-(JP1-Pad11)") (class "Default")
      (node (ref "JP1") (pin "11") (pinfunction "11_11") (pintype "passive"))
    )
    (net (code "85") (name "unconnected-(PCB1-88{slash}GPIO46_1V8-Pad88)") (class "Default")
      (node (ref "PCB1") (pin "88") (pinfunction "88/GPIO46_1V8_88") (pintype "bidirectional"))
    )
    (net (code "86") (name "unconnected-(PCB1-93{slash}DSI0_DN1*-Pad93)") (class "Default")
      (node (ref "PCB1") (pin "93") (pinfunction "93/DSI0_DN1*_93") (pintype "bidirectional"))
    )
    (net (code "87") (name "unconnected-(PCB1-94{slash}DSI1_DP0*-Pad94)") (class "Default")
      (node (ref "PCB1") (pin "94") (pinfunction "94/DSI1_DP0*_94") (pintype "bidirectional"))
    )
    (net (code "88") (name "unconnected-(PCB1-95{slash}DSI0_DP1*-Pad95)") (class "Default")
      (node (ref "PCB1") (pin "95") (pinfunction "95/DSI0_DP1*_95") (pintype "bidirectional"))
    )
    (net (code "89") (name "unconnected-(PCB1-96{slash}DSI1_DN0*-Pad96)") (class "Default")
      (node (ref "PCB1") (pin "96") (pinfunction "96/DSI1_DN0*_96") (pintype "bidirectional"))
    )
    (net (code "90") (name "unconnected-(PCB1-99{slash}DSI0_DN0*-Pad99)") (class "Default")
      (node (ref "PCB1") (pin "99") (pinfunction "99/DSI0_DN0*_99") (pintype "bidirectional"))
    )
    (net (code "91") (name "unconnected-(PCB1-100{slash}DSI1CP*-Pad100)") (class "Default")
      (node (ref "PCB1") (pin "100") (pinfunction "100/DSI1CP*_100") (pintype "bidirectional"))
    )
    (net (code "92") (name "unconnected-(PCB1-101{slash}DSI0_DP0*-Pad101)") (class "Default")
      (node (ref "PCB1") (pin "101") (pinfunction "101/DSI0_DP0*_101") (pintype "bidirectional"))
    )
    (net (code "93") (name "unconnected-(PCB1-102{slash}DSI1CN*-Pad102)") (class "Default")
      (node (ref "PCB1") (pin "102") (pinfunction "102/DSI1CN*_102") (pintype "bidirectional"))
    )
    (net (code "94") (name "unconnected-(PCB1-105{slash}DSI0_CN*-Pad105)") (class "Default")
      (node (ref "PCB1") (pin "105") (pinfunction "105/DSI0_CN*_105") (pintype "bidirectional"))
    )
    (net (code "95") (name "unconnected-(PCB1-106{slash}DSI1_DP3*-Pad106)") (class "Default")
      (node (ref "PCB1") (pin "106") (pinfunction "106/DSI1_DP3*_106") (pintype "bidirectional"))
    )
    (net (code "96") (name "unconnected-(PCB1-107{slash}DSI0_CP*-Pad107)") (class "Default")
      (node (ref "PCB1") (pin "107") (pinfunction "107/DSI0_CP*_107") (pintype "bidirectional"))
    )
    (net (code "97") (name "unconnected-(PCB1-108{slash}DSI1_DN3*-Pad108)") (class "Default")
      (node (ref "PCB1") (pin "108") (pinfunction "108/DSI1_DN3*_108") (pintype "bidirectional"))
    )
    (net (code "98") (name "unconnected-(PCB1-111{slash}HDMI_CK_N*-Pad111)") (class "Default")
      (node (ref "PCB1") (pin "111") (pinfunction "111/HDMI_CK_N*_111") (pintype "bidirectional"))
    )
    (net (code "99") (name "unconnected-(PCB1-112{slash}DSI1_DP2*-Pad112)") (class "Default")
      (node (ref "PCB1") (pin "112") (pinfunction "112/DSI1_DP2*_112") (pintype "bidirectional"))
    )
    (net (code "100") (name "unconnected-(PCB1-113{slash}HDMI_CK_P*-Pad113)") (class "Default")
      (node (ref "PCB1") (pin "113") (pinfunction "113/HDMI_CK_P*_113") (pintype "bidirectional"))
    )
    (net (code "101") (name "unconnected-(PCB1-114{slash}DSI1_DN2*-Pad114)") (class "Default")
      (node (ref "PCB1") (pin "114") (pinfunction "114/DSI1_DN2*_114") (pintype "bidirectional"))
    )
    (net (code "102") (name "unconnected-(PCB1-117{slash}HDMI_D0_N*-Pad117)") (class "Default")
      (node (ref "PCB1") (pin "117") (pinfunction "117/HDMI_D0_N*_117") (pintype "bidirectional"))
    )
    (net (code "103") (name "unconnected-(PCB1-118{slash}DSI1_DP1*-Pad118)") (class "Default")
      (node (ref "PCB1") (pin "118") (pinfunction "118/DSI1_DP1*_118") (pintype "bidirectional"))
    )
    (net (code "104") (name "unconnected-(PCB1-119{slash}HDMI_D0_P*-Pad119)") (class "Default")
      (node (ref "PCB1") (pin "119") (pinfunction "119/HDMI_D0_P*_119") (pintype "bidirectional"))
    )
    (net (code "105") (name "unconnected-(PCB1-120{slash}DSI1_DN1*-Pad120)") (class "Default")
      (node (ref "PCB1") (pin "120") (pinfunction "120/DSI1_DN1*_120") (pintype "bidirectional"))
    )
    (net (code "106") (name "unconnected-(PCB1-123{slash}HDMI_D1_N*-Pad123)") (class "Default")
      (node (ref "PCB1") (pin "123") (pinfunction "123/HDMI_D1_N*_123") (pintype "bidirectional"))
    )
    (net (code "107") (name "unconnected-(PCB1-124{slash}NC-Pad124)") (class "Default")
      (node (ref "PCB1") (pin "124") (pinfunction "124/NC_124") (pintype "bidirectional"))
    )
    (net (code "108") (name "unconnected-(PCB1-125{slash}HDMI_D1_P*-Pad125)") (class "Default")
      (node (ref "PCB1") (pin "125") (pinfunction "125/HDMI_D1_P*_125") (pintype "bidirectional"))
    )
    (net (code "109") (name "unconnected-(PCB1-126{slash}NC-Pad126)") (class "Default")
      (node (ref "PCB1") (pin "126") (pinfunction "126/NC_126") (pintype "bidirectional"))
    )
    (net (code "110") (name "unconnected-(PCB1-128{slash}NC-Pad128)") (class "Default")
      (node (ref "PCB1") (pin "128") (pinfunction "128/NC_128") (pintype "bidirectional"))
    )
    (net (code "111") (name "unconnected-(PCB1-129{slash}HDMI_D2_N*-Pad129)") (class "Default")
      (node (ref "PCB1") (pin "129") (pinfunction "129/HDMI_D2_N*_129") (pintype "bidirectional"))
    )
    (net (code "112") (name "unconnected-(PCB1-130{slash}NC-Pad130)") (class "Default")
      (node (ref "PCB1") (pin "130") (pinfunction "130/NC_130") (pintype "bidirectional"))
    )
    (net (code "113") (name "unconnected-(PCB1-131{slash}HDMI_D2_P*-Pad131)") (class "Default")
      (node (ref "PCB1") (pin "131") (pinfunction "131/HDMI_D2_P*_131") (pintype "bidirectional"))
    )
    (net (code "114") (name "unconnected-(PCB1-132{slash}NC-Pad132)") (class "Default")
      (node (ref "PCB1") (pin "132") (pinfunction "132/NC_132") (pintype "bidirectional"))
    )
    (net (code "115") (name "unconnected-(PCB1-135{slash}CAM1_DP3*-Pad135)") (class "Default")
      (node (ref "PCB1") (pin "135") (pinfunction "135/CAM1_DP3*_135") (pintype "bidirectional"))
    )
    (net (code "116") (name "unconnected-(PCB1-136{slash}CAM0_DP0*-Pad136)") (class "Default")
      (node (ref "PCB1") (pin "136") (pinfunction "136/CAM0_DP0*_136") (pintype "bidirectional"))
    )
    (net (code "117") (name "unconnected-(PCB1-137{slash}CAM1_DN3*-Pad137)") (class "Default")
      (node (ref "PCB1") (pin "137") (pinfunction "137/CAM1_DN3*_137") (pintype "bidirectional"))
    )
    (net (code "118") (name "unconnected-(PCB1-138{slash}CAM0_DN0*-Pad138)") (class "Default")
      (node (ref "PCB1") (pin "138") (pinfunction "138/CAM0_DN0*_138") (pintype "bidirectional"))
    )
    (net (code "119") (name "unconnected-(PCB1-141{slash}CAM1_DP2*-Pad141)") (class "Default")
      (node (ref "PCB1") (pin "141") (pinfunction "141/CAM1_DP2*_141") (pintype "bidirectional"))
    )
    (net (code "120") (name "unconnected-(PCB1-142{slash}CAM0_CP*-Pad142)") (class "Default")
      (node (ref "PCB1") (pin "142") (pinfunction "142/CAM0_CP*_142") (pintype "bidirectional"))
    )
    (net (code "121") (name "unconnected-(PCB1-143{slash}CAM1_DN2*-Pad143)") (class "Default")
      (node (ref "PCB1") (pin "143") (pinfunction "143/CAM1_DN2*_143") (pintype "bidirectional"))
    )
    (net (code "122") (name "unconnected-(PCB1-144{slash}CAM0_CN*-Pad144)") (class "Default")
      (node (ref "PCB1") (pin "144") (pinfunction "144/CAM0_CN*_144") (pintype "bidirectional"))
    )
    (net (code "123") (name "unconnected-(PCB1-147{slash}CAM1_CP*-Pad147)") (class "Default")
      (node (ref "PCB1") (pin "147") (pinfunction "147/CAM1_CP*_147") (pintype "bidirectional"))
    )
    (net (code "124") (name "unconnected-(PCB1-148{slash}CAM0_DP1*-Pad148)") (class "Default")
      (node (ref "PCB1") (pin "148") (pinfunction "148/CAM0_DP1*_148") (pintype "bidirectional"))
    )
    (net (code "125") (name "unconnected-(PCB1-149{slash}CAM1_CN*-Pad149)") (class "Default")
      (node (ref "PCB1") (pin "149") (pinfunction "149/CAM1_CN*_149") (pintype "bidirectional"))
    )
    (net (code "126") (name "unconnected-(PCB1-150{slash}CAM0_DN1*-Pad150)") (class "Default")
      (node (ref "PCB1") (pin "150") (pinfunction "150/CAM0_DN1*_150") (pintype "bidirectional"))
    )
    (net (code "127") (name "unconnected-(PCB1-153{slash}CAM1_DP1*-Pad153)") (class "Default")
      (node (ref "PCB1") (pin "153") (pinfunction "153/CAM1_DP1*_153") (pintype "bidirectional"))
    )
    (net (code "128") (name "unconnected-(PCB1-154{slash}NC-Pad154)") (class "Default")
      (node (ref "PCB1") (pin "154") (pinfunction "154/NC_154") (pintype "bidirectional"))
    )
    (net (code "129") (name "unconnected-(PCB1-155{slash}CAM1_DN1*-Pad155)") (class "Default")
      (node (ref "PCB1") (pin "155") (pinfunction "155/CAM1_DN1*_155") (pintype "bidirectional"))
    )
    (net (code "130") (name "unconnected-(PCB1-156{slash}NC-Pad156)") (class "Default")
      (node (ref "PCB1") (pin "156") (pinfunction "156/NC_156") (pintype "bidirectional"))
    )
    (net (code "131") (name "unconnected-(PCB1-158{slash}NC-Pad158)") (class "Default")
      (node (ref "PCB1") (pin "158") (pinfunction "158/NC_158") (pintype "bidirectional"))
    )
    (net (code "132") (name "unconnected-(PCB1-159{slash}CAM1_DP0*-Pad159)") (class "Default")
      (node (ref "PCB1") (pin "159") (pinfunction "159/CAM1_DP0*_159") (pintype "bidirectional"))
    )
    (net (code "133") (name "unconnected-(PCB1-160{slash}NC-Pad160)") (class "Default")
      (node (ref "PCB1") (pin "160") (pinfunction "160/NC_160") (pintype "bidirectional"))
    )
    (net (code "134") (name "unconnected-(PCB1-161{slash}CAM1_DN0*-Pad161)") (class "Default")
      (node (ref "PCB1") (pin "161") (pinfunction "161/CAM1_DN0*_161") (pintype "bidirectional"))
    )
    (net (code "135") (name "unconnected-(PCB1-162{slash}NC-Pad162)") (class "Default")
      (node (ref "PCB1") (pin "162") (pinfunction "162/NC_162") (pintype "bidirectional"))
    )
    (net (code "136") (name "unconnected-(PCB1-166{slash}TVDAC-Pad166)") (class "Default")
      (node (ref "PCB1") (pin "166") (pinfunction "166/TVDAC_166") (pintype "bidirectional"))
    )
    (net (code "137") (name "unconnected-(PCB1-168{slash}USB_OTGID-Pad168)") (class "Default")
      (node (ref "PCB1") (pin "168") (pinfunction "168/USB_OTGID_168") (pintype "bidirectional"))
    )
    (net (code "138") (name "unconnected-(PCB1-171{slash}HDMI_CEC-Pad171)") (class "Default")
      (node (ref "PCB1") (pin "171") (pinfunction "171/HDMI_CEC_171") (pintype "bidirectional"))
    )
    (net (code "139") (name "unconnected-(PCB1-172{slash}VC_TRST_N-Pad172)") (class "Default")
      (node (ref "PCB1") (pin "172") (pinfunction "172/VC_TRST_N_172") (pintype "bidirectional"))
    )
    (net (code "140") (name "unconnected-(PCB1-173{slash}HDMI_SDA-Pad173)") (class "Default")
      (node (ref "PCB1") (pin "173") (pinfunction "173/HDMI_SDA_173") (pintype "bidirectional"))
    )
    (net (code "141") (name "unconnected-(PCB1-174{slash}VC_TDI-Pad174)") (class "Default")
      (node (ref "PCB1") (pin "174") (pinfunction "174/VC_TDI_174") (pintype "bidirectional"))
    )
    (net (code "142") (name "unconnected-(PCB1-175{slash}HDMI_SCL-Pad175)") (class "Default")
      (node (ref "PCB1") (pin "175") (pinfunction "175/HDMI_SCL_175") (pintype "bidirectional"))
    )
    (net (code "143") (name "unconnected-(PCB1-176{slash}VC_TMS-Pad176)") (class "Default")
      (node (ref "PCB1") (pin "176") (pinfunction "176/VC_TMS_176") (pintype "bidirectional"))
    )
    (net (code "144") (name "unconnected-(PCB1-178{slash}VC_TDO-Pad178)") (class "Default")
      (node (ref "PCB1") (pin "178") (pinfunction "178/VC_TDO_178") (pintype "bidirectional"))
    )
    (net (code "145") (name "unconnected-(PCB1-179{slash}VDD_CORE-Pad179)") (class "Default")
      (node (ref "PCB1") (pin "179") (pinfunction "179/VDD_CORE_179") (pintype "bidirectional"))
    )
    (net (code "146") (name "unconnected-(PCB1-180{slash}VC_TCK-Pad180)") (class "Default")
      (node (ref "PCB1") (pin "180") (pinfunction "180/VC_TCK_180") (pintype "bidirectional"))
    )
    (net (code "147") (name "unconnected-(U1-NC-Pad5)") (class "Default")
      (node (ref "U1") (pin "5") (pinfunction "NC_5") (pintype "no_connect"))
    )
    (net (code "148") (name "unconnected-(U1-NC-Pad11)") (class "Default")
      (node (ref "U1") (pin "11") (pinfunction "NC_11") (pintype "no_connect"))
    )
  )
)
